# DDS.net
KiCad netlist of a schematic drawn in Altium Designer
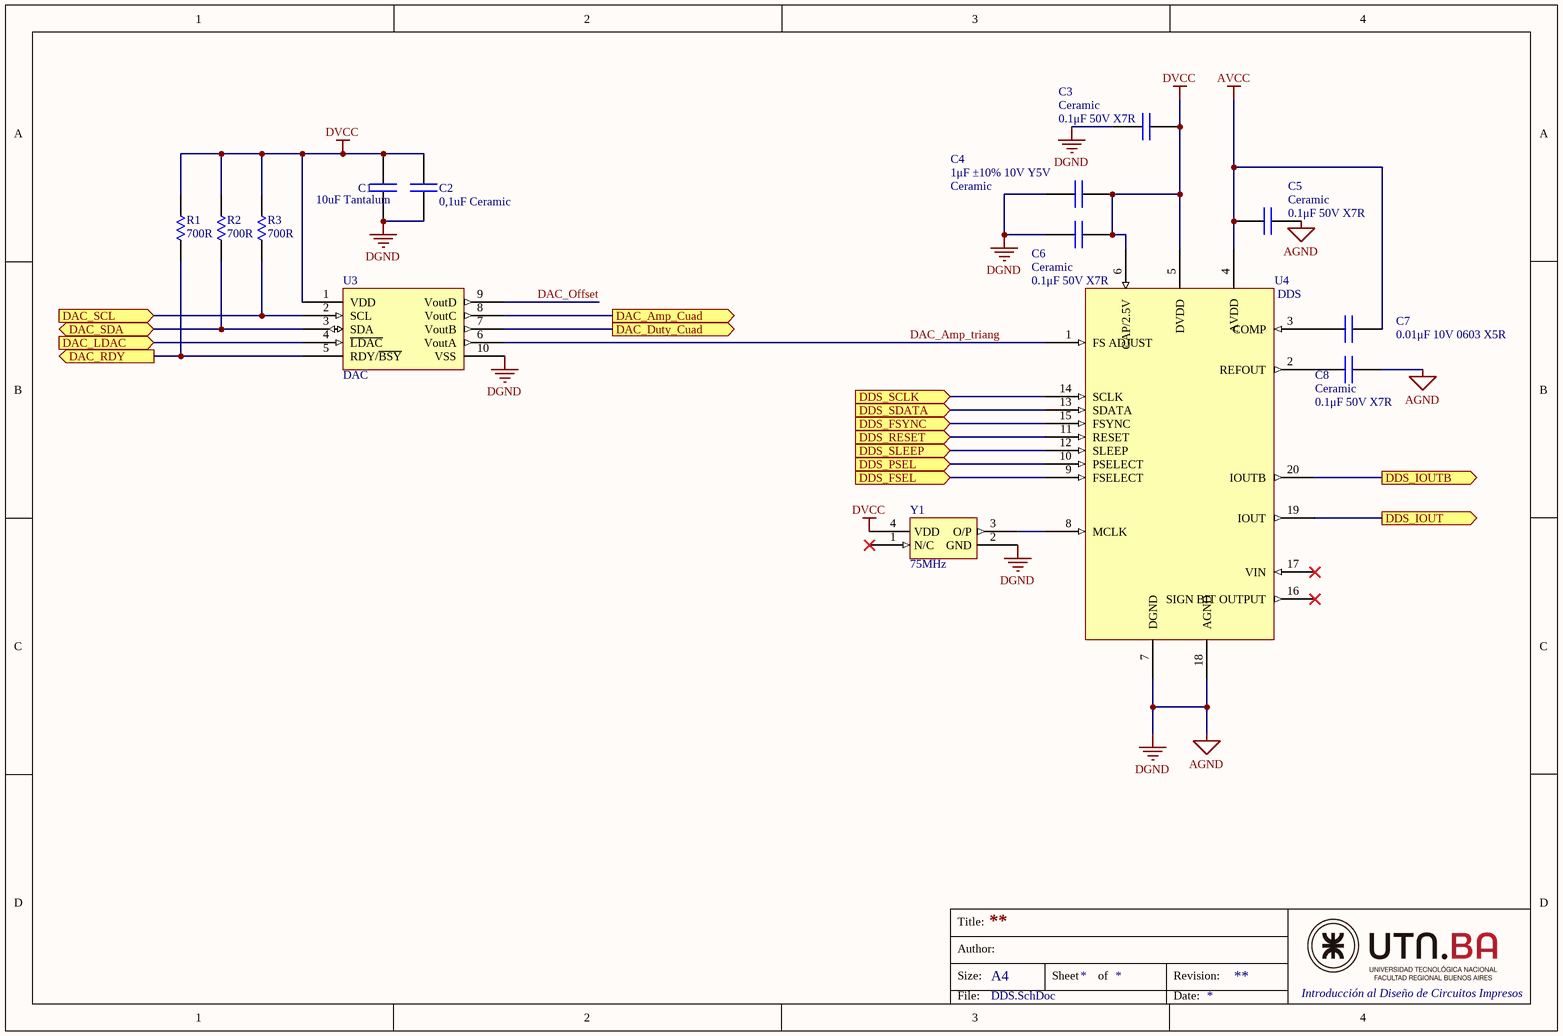
[diagram p0: DDS.SchDoc]

(export (version "E")
  (design (tool "Eeschema 10.0.6"))
  (components
    (comp (ref "C1")
      (value "10uF Tantalum")
      (description "Capacitor")
      (libsource (lib "Gen_func") (part "Cap"))
    )
    (comp (ref "C2")
      (value "0,1uF Ceramic")
      (description "Capacitor")
      (libsource (lib "Gen_func") (part "Cap"))
    )
    (comp (ref "C3")
      (value "0.1μF 50V X7R")
      (description "Capacitor")
      (fields (field (name "TYPE") "Ceramic"))
      (libsource (lib "Gen_func") (part "Cap"))
    )
    (comp (ref "C4")
      (value "1μF ±10% 10V Y5V")
      (description "Capacitor")
      (fields (field (name "TYPE") "Ceramic"))
      (libsource (lib "Gen_func") (part "Cap"))
    )
    (comp (ref "C5")
      (value "0.1μF 50V X7R")
      (description "Capacitor")
      (fields (field (name "TYPE") "Ceramic"))
      (libsource (lib "Gen_func") (part "Cap"))
    )
    (comp (ref "C6")
      (value "0.1μF 50V X7R")
      (description "Capacitor")
      (fields (field (name "TYPE") "Ceramic"))
      (libsource (lib "Gen_func") (part "Cap"))
    )
    (comp (ref "C7")
      (value "0.01μF 10V 0603 X5R")
      (description "Capacitor")
      (libsource (lib "Gen_func") (part "Cap"))
    )
    (comp (ref "C8")
      (value "0.1μF 50V X7R")
      (description "Capacitor")
      (fields (field (name "TYPE") "Ceramic"))
      (libsource (lib "Gen_func") (part "Cap"))
    )
    (comp (ref "R1") (value "700R") (description "Resistor") (libsource (lib "Gen_func") (part "Res")))
    (comp (ref "R2") (value "700R") (description "Resistor") (libsource (lib "Gen_func") (part "Res")))
    (comp (ref "R3") (value "700R") (description "Resistor") (libsource (lib "Gen_func") (part "Res")))
    (comp (ref "U3") (value "DAC") (description "DAC x4 I2C") (libsource (lib "Gen_func") (part "DAC")))
    (comp (ref "U4") (value "DDS") (description "DDS 50MHz") (libsource (lib "Gen_func") (part "DDS")))
    (comp (ref "Y1")
      (value "75MHz")
      (description "Crystal oscillator")
      (libsource (lib "Gen_func") (part "XTAL"))
    )
  )
  (nets
    (net (code "1") (name "/DAC_Amp_Cuad") (class "Default")
      (node (ref "U3") (pin "8") (pinfunction "VoutC_8") (pintype "output"))
    )
    (net (code "2") (name "/DAC_Amp_triang") (class "Default")
      (node (ref "U3") (pin "6") (pinfunction "VoutA_6") (pintype "output"))
      (node (ref "U4") (pin "1") (pinfunction "FS_ADJUST_1") (pintype "input"))
    )
    (net (code "3") (name "/DAC_Duty_Cuad") (class "Default")
      (node (ref "U3") (pin "7") (pinfunction "VoutB_7") (pintype "output"))
    )
    (net (code "4") (name "/DAC_LDAC") (class "Default")
      (node (ref "U3") (pin "4") (pinfunction "~{LDAC}_4") (pintype "input"))
    )
    (net (code "5") (name "/DAC_Offset") (class "Default")
      (node (ref "U3") (pin "9") (pinfunction "VoutD_9") (pintype "output"))
    )
    (net (code "6") (name "/DAC_RDY") (class "Default")
      (node (ref "R1") (pin "1") (pinfunction "1_1") (pintype "passive"))
      (node (ref "U3") (pin "5") (pinfunction "RDY/~{BSY}_5") (pintype "open_collector"))
    )
    (net (code "7") (name "/DAC_SCL") (class "Default")
      (node (ref "R3") (pin "1") (pinfunction "1_1") (pintype "passive"))
      (node (ref "U3") (pin "2") (pinfunction "SCL_2") (pintype "input"))
    )
    (net (code "8") (name "/DAC_SDA") (class "Default")
      (node (ref "R2") (pin "1") (pinfunction "1_1") (pintype "passive"))
      (node (ref "U3") (pin "3") (pinfunction "SDA_3") (pintype "bidirectional"))
    )
    (net (code "9") (name "/DDS_FSEL") (class "Default")
      (node (ref "U4") (pin "9") (pinfunction "FSELECT_9") (pintype "input"))
    )
    (net (code "10") (name "/DDS_FSYNC") (class "Default")
      (node (ref "U4") (pin "15") (pinfunction "FSYNC_15") (pintype "input"))
    )
    (net (code "11") (name "/DDS_IOUT") (class "Default")
      (node (ref "U4") (pin "19") (pinfunction "IOUT_19") (pintype "output"))
    )
    (net (code "12") (name "/DDS_IOUTB") (class "Default")
      (node (ref "U4") (pin "20") (pinfunction "IOUTB_20") (pintype "output"))
    )
    (net (code "13") (name "/DDS_PSEL") (class "Default")
      (node (ref "U4") (pin "10") (pinfunction "PSELECT_10") (pintype "input"))
    )
    (net (code "14") (name "/DDS_RESET") (class "Default")
      (node (ref "U4") (pin "11") (pinfunction "RESET_11") (pintype "input"))
    )
    (net (code "15") (name "/DDS_SCLK") (class "Default")
      (node (ref "U4") (pin "14") (pinfunction "SCLK_14") (pintype "input"))
    )
    (net (code "16") (name "/DDS_SDATA") (class "Default")
      (node (ref "U4") (pin "13") (pinfunction "SDATA_13") (pintype "input"))
    )
    (net (code "17") (name "/DDS_SLEEP") (class "Default")
      (node (ref "U4") (pin "12") (pinfunction "SLEEP_12") (pintype "input"))
    )
    (net (code "18") (name "AGND") (class "Default")
      (node (ref "C1") (pin "2") (pinfunction "2_2") (pintype "passive"))
      (node (ref "C2") (pin "2") (pinfunction "2_2") (pintype "passive"))
      (node (ref "C3") (pin "1") (pinfunction "1_1") (pintype "passive"))
      (node (ref "C4") (pin "1") (pinfunction "1_1") (pintype "passive"))
      (node (ref "C5") (pin "2") (pinfunction "2_2") (pintype "passive"))
      (node (ref "C6") (pin "1") (pinfunction "1_1") (pintype "passive"))
      (node (ref "C8") (pin "2") (pinfunction "2_2") (pintype "passive"))
      (node (ref "U3") (pin "10") (pinfunction "VSS_10") (pintype "power_in"))
      (node (ref "U4") (pin "18") (pinfunction "AGND_18") (pintype "power_in"))
      (node (ref "U4") (pin "7") (pinfunction "DGND_7") (pintype "power_in"))
      (node (ref "Y1") (pin "2") (pinfunction "GND_2") (pintype "power_in"))
    )
    (net (code "19") (name "AVCC") (class "Default")
      (node (ref "C5") (pin "1") (pinfunction "1_1") (pintype "passive"))
      (node (ref "C7") (pin "1") (pinfunction "1_1") (pintype "passive"))
      (node (ref "U4") (pin "4") (pinfunction "AVDD_4") (pintype "power_in"))
    )
    (net (code "20") (name "DVCC") (class "Default")
      (node (ref "C1") (pin "1") (pinfunction "1_1") (pintype "passive"))
      (node (ref "C2") (pin "1") (pinfunction "1_1") (pintype "passive"))
      (node (ref "C3") (pin "2") (pinfunction "2_2") (pintype "passive"))
      (node (ref "C4") (pin "2") (pinfunction "2_2") (pintype "passive"))
      (node (ref "C6") (pin "2") (pinfunction "2_2") (pintype "passive"))
      (node (ref "R1") (pin "2") (pinfunction "2_2") (pintype "passive"))
      (node (ref "R2") (pin "2") (pinfunction "2_2") (pintype "passive"))
      (node (ref "R3") (pin "2") (pinfunction "2_2") (pintype "passive"))
      (node (ref "U3") (pin "1") (pinfunction "VDD_1") (pintype "power_in"))
      (node (ref "U4") (pin "5") (pinfunction "DVDD_5") (pintype "power_in"))
      (node (ref "U4") (pin "6") (pinfunction "CAP/2.5V_6") (pintype "input"))
      (node (ref "Y1") (pin "4") (pinfunction "VDD_4") (pintype "power_in"))
    )
    (net (code "21") (name "Net-(U4-COMP)") (class "Default")
      (node (ref "C7") (pin "2") (pinfunction "2_2") (pintype "passive"))
      (node (ref "U4") (pin "3") (pinfunction "COMP_3") (pintype "input"))
    )
    (net (code "22") (name "Net-(U4-MCLK)") (class "Default")
      (node (ref "U4") (pin "8") (pinfunction "MCLK_8") (pintype "input"))
      (node (ref "Y1") (pin "3") (pinfunction "O/P_3") (pintype "output"))
    )
    (net (code "23") (name "Net-(U4-REFOUT)") (class "Default")
      (node (ref "C8") (pin "1") (pinfunction "1_1") (pintype "passive"))
      (node (ref "U4") (pin "2") (pinfunction "REFOUT_2") (pintype "output"))
    )
    (net (code "24") (name "unconnected-(U4-SIGN_BIT_OUTPUT-Pad16)") (class "Default")
      (node (ref "U4") (pin "16") (pinfunction "SIGN_BIT_OUTPUT_16") (pintype "output+no_connect"))
    )
    (net (code "25") (name "unconnected-(U4-VIN-Pad17)") (class "Default")
      (node (ref "U4") (pin "17") (pinfunction "VIN_17") (pintype "input+no_connect"))
    )
    (net (code "26") (name "unconnected-(Y1-N{slash}C-Pad1)") (class "Default")
      (node (ref "Y1") (pin "1") (pinfunction "N/C_1") (pintype "input+no_connect"))
    )
  )
)
